# USBtoTTL.net
KiCad netlist of a schematic drawn in Altium Designer
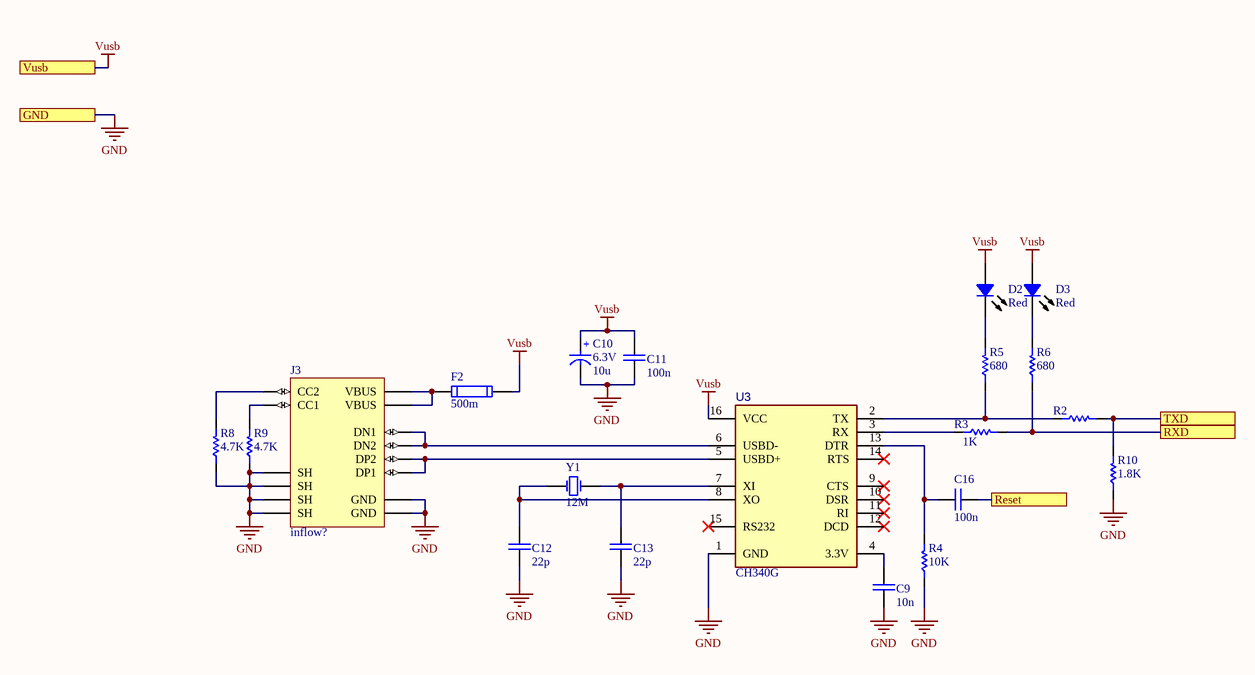
[diagram p0: USBtoTTL.SchDoc]

(export (version "E")
  (design (tool "Eeschema 10.0.6"))
  (components
    (comp (ref "C9")
      (value "10n")
      (footprint "CAP 0805/2012")
      (description "Bipolar ceramic capacitor SMD")
      (fields (field (name "VALIDATION") "Valid"))
      (libsource (lib "aKaReZa") (part "Cap_Multi_SMD_0805"))
    )
    (comp (ref "C10")
      (value "10u")
      (footprint "SMT_C_Tantalum_A")
      (description "Tantalum Capacitor,TAJ Series-SMD")
      (fields (field (name "RATING") "6.3V") (field (name "VALIDATION") "Valid"))
      (libsource (lib "aKaReZa") (part "Cap_Tantalum"))
    )
    (comp (ref "C11")
      (value "100n")
      (footprint "CAP 0805/2012")
      (description "Bipolar ceramic capacitor SMD")
      (fields (field (name "VALIDATION") "Valid"))
      (libsource (lib "aKaReZa") (part "Cap_Multi_SMD_100nF_0805"))
    )
    (comp (ref "C12")
      (value "22p")
      (footprint "CAP 0805/2012")
      (description "Bipolar ceramic capacitor SMD")
      (fields (field (name "VALIDATION") "Valid"))
      (libsource (lib "aKaReZa") (part "Cap_Multi_SMD_0805"))
    )
    (comp (ref "C13")
      (value "22p")
      (footprint "CAP 0805/2012")
      (description "Bipolar ceramic capacitor SMD")
      (fields (field (name "VALIDATION") "Valid"))
      (libsource (lib "aKaReZa") (part "Cap_Multi_SMD_0805"))
    )
    (comp (ref "C16")
      (value "100n")
      (footprint "CAP 0805/2012")
      (description "Bipolar ceramic capacitor SMD")
      (fields (field (name "VALIDATION") "Valid"))
      (libsource (lib "aKaReZa") (part "Cap_Multi_SMD_100nF_0805"))
    )
    (comp (ref "D2")
      (value "Red")
      (footprint "LED 0805/2012 RED")
      (description "LED")
      (fields (field (name "VALIDATION") "Valid"))
      (libsource (lib "aKaReZa") (part "Semi_LED_SMD"))
    )
    (comp (ref "D3")
      (value "Red")
      (footprint "LED 0805/2012 RED")
      (description "LED")
      (fields (field (name "VALIDATION") "Valid"))
      (libsource (lib "aKaReZa") (part "Semi_LED_SMD"))
    )
    (comp (ref "F2")
      (value "500m")
      (footprint "1206_F")
      (description "Short circiut  protection")
      (fields (field (name "VALIDATION") "Valid"))
      (libsource (lib "aKaReZa") (part "Other_Elec_Fuse_SMD"))
    )
    (comp (ref "J3")
      (value "12b")
      (footprint "HRO_TYPE-C-31-M-12 - Extended")
      (description "USB C Female Connector")
      (fields (field (name "INFLOW") "inflow?") (field (name "VALIDATION") "Valid"))
      (libsource (lib "aKaReZa") (part "Con_USB_C"))
    )
    (comp (ref "R2")
      (value "1K")
      (footprint "RES 0805 (2012X06L)")
      (description "Resistor")
      (fields (field (name "VALIDATION") "Valid"))
      (libsource (lib "aKaReZa") (part "Res_SMD_0805"))
    )
    (comp (ref "R3")
      (value "1K")
      (footprint "RES 0805 (2012X06L)")
      (description "Resistor")
      (fields (field (name "VALIDATION") "Valid"))
      (libsource (lib "aKaReZa") (part "Res_SMD_0805"))
    )
    (comp (ref "R4")
      (value "10K")
      (footprint "RES 0805 (2012X06L)")
      (description "Resistor")
      (fields (field (name "VALIDATION") "Valid"))
      (libsource (lib "aKaReZa") (part "Res_SMD_0805"))
    )
    (comp (ref "R5")
      (value "680")
      (footprint "RES 0805 (2012X06L)")
      (description "Resistor")
      (fields (field (name "VALIDATION") "Valid"))
      (libsource (lib "aKaReZa") (part "Res_SMD_0805"))
    )
    (comp (ref "R6")
      (value "680")
      (footprint "RES 0805 (2012X06L)")
      (description "Resistor")
      (fields (field (name "VALIDATION") "Valid"))
      (libsource (lib "aKaReZa") (part "Res_SMD_0805"))
    )
    (comp (ref "R8")
      (value "4.7K")
      (footprint "RES 0805 (2012X06L)")
      (description "Resistor")
      (fields (field (name "VALIDATION") "Valid"))
      (libsource (lib "aKaReZa") (part "Res_SMD_0805"))
    )
    (comp (ref "R9")
      (value "4.7K")
      (footprint "RES 0805 (2012X06L)")
      (description "Resistor")
      (fields (field (name "VALIDATION") "Valid"))
      (libsource (lib "aKaReZa") (part "Res_SMD_0805"))
    )
    (comp (ref "R10")
      (value "1.8K")
      (footprint "RES 0805 (2012X06L)")
      (description "Resistor")
      (fields (field (name "VALIDATION") "Valid"))
      (libsource (lib "aKaReZa") (part "Res_SMD_0805"))
    )
    (comp (ref "U3")
      (value "CH340G")
      (footprint "SO16_M")
      (description "TTL To USB Chip")
      (fields (field (name "VALIDATION") "Valid"))
      (libsource (lib "aKaReZa") (part "IC_Converter_CH340G"))
    )
    (comp (ref "Y1")
      (value "12M")
      (footprint "Crystal SMD")
      (description "Crystal Oscillator")
      (fields (field (name "VALIDATION") "Valid"))
      (libsource (lib "aKaReZa") (part "Other_Elec_Xtal_SMD"))
    )
  )
  (nets
    (net (code "1") (name "/RXD") (class "Default")
      (node (ref "R3") (pin "2") (pinfunction "2_2") (pintype "passive"))
      (node (ref "R6") (pin "1") (pinfunction "1_1") (pintype "passive"))
    )
    (net (code "2") (name "/Reset") (class "Default")
      (node (ref "C16") (pin "2") (pinfunction "2_2") (pintype "passive"))
    )
    (net (code "3") (name "/TXD") (class "Default")
      (node (ref "R10") (pin "2") (pinfunction "2_2") (pintype "passive"))
      (node (ref "R2") (pin "2") (pinfunction "2_2") (pintype "passive"))
    )
    (net (code "4") (name "GND") (class "Default")
      (node (ref "C10") (pin "2") (pinfunction "-_2") (pintype "passive"))
      (node (ref "C11") (pin "2") (pinfunction "2_2") (pintype "passive"))
      (node (ref "C12") (pin "2") (pinfunction "2_2") (pintype "passive"))
      (node (ref "C13") (pin "2") (pinfunction "2_2") (pintype "passive"))
      (node (ref "C9") (pin "2") (pinfunction "2_2") (pintype "passive"))
      (node (ref "J3") (pin "A1_B12") (pinfunction "GND_A1_B12") (pintype "power_in"))
      (node (ref "J3") (pin "B1_A12") (pinfunction "GND_B1_A12") (pintype "power_in"))
      (node (ref "J3") (pin "S1") (pinfunction "SH_S1") (pintype "passive"))
      (node (ref "J3") (pin "S2") (pinfunction "SH_S2") (pintype "passive"))
      (node (ref "J3") (pin "S3") (pinfunction "SH_S3") (pintype "passive"))
      (node (ref "J3") (pin "S4") (pinfunction "SH_S4") (pintype "passive"))
      (node (ref "R10") (pin "1") (pinfunction "1_1") (pintype "passive"))
      (node (ref "R4") (pin "1") (pinfunction "1_1") (pintype "passive"))
      (node (ref "R8") (pin "1") (pinfunction "1_1") (pintype "passive"))
      (node (ref "R9") (pin "1") (pinfunction "1_1") (pintype "passive"))
      (node (ref "U3") (pin "1") (pinfunction "GND_1") (pintype "passive"))
    )
    (net (code "5") (name "Net-(D2-Pad2)") (class "Default")
      (node (ref "D2") (pin "2") (pinfunction "2_2") (pintype "passive"))
      (node (ref "R5") (pin "2") (pinfunction "2_2") (pintype "passive"))
    )
    (net (code "6") (name "Net-(D3-Pad2)") (class "Default")
      (node (ref "D3") (pin "2") (pinfunction "2_2") (pintype "passive"))
      (node (ref "R6") (pin "2") (pinfunction "2_2") (pintype "passive"))
    )
    (net (code "7") (name "Net-(F2-Pad1)") (class "Default")
      (node (ref "F2") (pin "1") (pinfunction "1_1") (pintype "passive"))
      (node (ref "J3") (pin "A4_B9") (pinfunction "VBUS_A4_B9") (pintype "power_in"))
      (node (ref "J3") (pin "B4_A9") (pinfunction "VBUS_B4_A9") (pintype "power_in"))
    )
    (net (code "8") (name "Net-(J3-CC1)") (class "Default")
      (node (ref "J3") (pin "A5") (pinfunction "CC1_A5") (pintype "bidirectional"))
      (node (ref "R9") (pin "2") (pinfunction "2_2") (pintype "passive"))
    )
    (net (code "9") (name "Net-(J3-CC2)") (class "Default")
      (node (ref "J3") (pin "B5") (pinfunction "CC2_B5") (pintype "bidirectional"))
      (node (ref "R8") (pin "2") (pinfunction "2_2") (pintype "passive"))
    )
    (net (code "10") (name "Net-(J3-DN1)") (class "Default")
      (node (ref "J3") (pin "A7") (pinfunction "DN1_A7") (pintype "bidirectional"))
      (node (ref "J3") (pin "B7") (pinfunction "DN2_B7") (pintype "bidirectional"))
      (node (ref "U3") (pin "6") (pinfunction "USBD-_6") (pintype "passive"))
    )
    (net (code "11") (name "Net-(J3-DP1)") (class "Default")
      (node (ref "J3") (pin "A6") (pinfunction "DP1_A6") (pintype "bidirectional"))
      (node (ref "J3") (pin "B6") (pinfunction "DP2_B6") (pintype "bidirectional"))
      (node (ref "U3") (pin "5") (pinfunction "USBD+_5") (pintype "passive"))
    )
    (net (code "12") (name "Net-(U3-3.3V)") (class "Default")
      (node (ref "C9") (pin "1") (pinfunction "1_1") (pintype "passive"))
      (node (ref "U3") (pin "4") (pinfunction "3.3V_4") (pintype "passive"))
    )
    (net (code "13") (name "Net-(U3-DTR)") (class "Default")
      (node (ref "C16") (pin "1") (pinfunction "1_1") (pintype "passive"))
      (node (ref "R4") (pin "2") (pinfunction "2_2") (pintype "passive"))
      (node (ref "U3") (pin "13") (pinfunction "DTR_13") (pintype "passive"))
    )
    (net (code "14") (name "Net-(U3-RX)") (class "Default")
      (node (ref "R3") (pin "1") (pinfunction "1_1") (pintype "passive"))
      (node (ref "U3") (pin "3") (pinfunction "RX_3") (pintype "passive"))
    )
    (net (code "15") (name "Net-(U3-TX)") (class "Default")
      (node (ref "R2") (pin "1") (pinfunction "1_1") (pintype "passive"))
      (node (ref "R5") (pin "1") (pinfunction "1_1") (pintype "passive"))
      (node (ref "U3") (pin "2") (pinfunction "TX_2") (pintype "passive"))
    )
    (net (code "16") (name "Net-(U3-XI)") (class "Default")
      (node (ref "C13") (pin "1") (pinfunction "1_1") (pintype "passive"))
      (node (ref "U3") (pin "7") (pinfunction "XI_7") (pintype "passive"))
      (node (ref "Y1") (pin "2") (pinfunction "OSC2_2") (pintype "passive"))
    )
    (net (code "17") (name "Net-(U3-XO)") (class "Default")
      (node (ref "C12") (pin "1") (pinfunction "1_1") (pintype "passive"))
      (node (ref "U3") (pin "8") (pinfunction "XO_8") (pintype "passive"))
      (node (ref "Y1") (pin "1") (pinfunction "OSC1_1") (pintype "passive"))
    )
    (net (code "18") (name "Vusb") (class "Default")
      (node (ref "C10") (pin "1") (pinfunction "+_1") (pintype "passive"))
      (node (ref "C11") (pin "1") (pinfunction "1_1") (pintype "passive"))
      (node (ref "D2") (pin "1") (pinfunction "1_1") (pintype "passive"))
      (node (ref "D3") (pin "1") (pinfunction "1_1") (pintype "passive"))
      (node (ref "F2") (pin "2") (pinfunction "2_2") (pintype "passive"))
      (node (ref "U3") (pin "16") (pinfunction "VCC_16") (pintype "passive"))
    )
    (net (code "19") (name "unconnected-(U3-CTS-Pad9)") (class "Default")
      (node (ref "U3") (pin "9") (pinfunction "CTS_9") (pintype "passive+no_connect"))
    )
    (net (code "20") (name "unconnected-(U3-DCD-Pad12)") (class "Default")
      (node (ref "U3") (pin "12") (pinfunction "DCD_12") (pintype "passive+no_connect"))
    )
    (net (code "21") (name "unconnected-(U3-DSR-Pad10)") (class "Default")
      (node (ref "U3") (pin "10") (pinfunction "DSR_10") (pintype "passive+no_connect"))
    )
    (net (code "22") (name "unconnected-(U3-RI-Pad11)") (class "Default")
      (node (ref "U3") (pin "11") (pinfunction "RI_11") (pintype "passive+no_connect"))
    )
    (net (code "23") (name "unconnected-(U3-RS232-Pad15)") (class "Default")
      (node (ref "U3") (pin "15") (pinfunction "RS232_15") (pintype "passive+no_connect"))
    )
    (net (code "24") (name "unconnected-(U3-RTS-Pad14)") (class "Default")
      (node (ref "U3") (pin "14") (pinfunction "RTS_14") (pintype "passive+no_connect"))
    )
  )
)
